# Display.net
KiCad netlist of a schematic drawn in Altium Designer
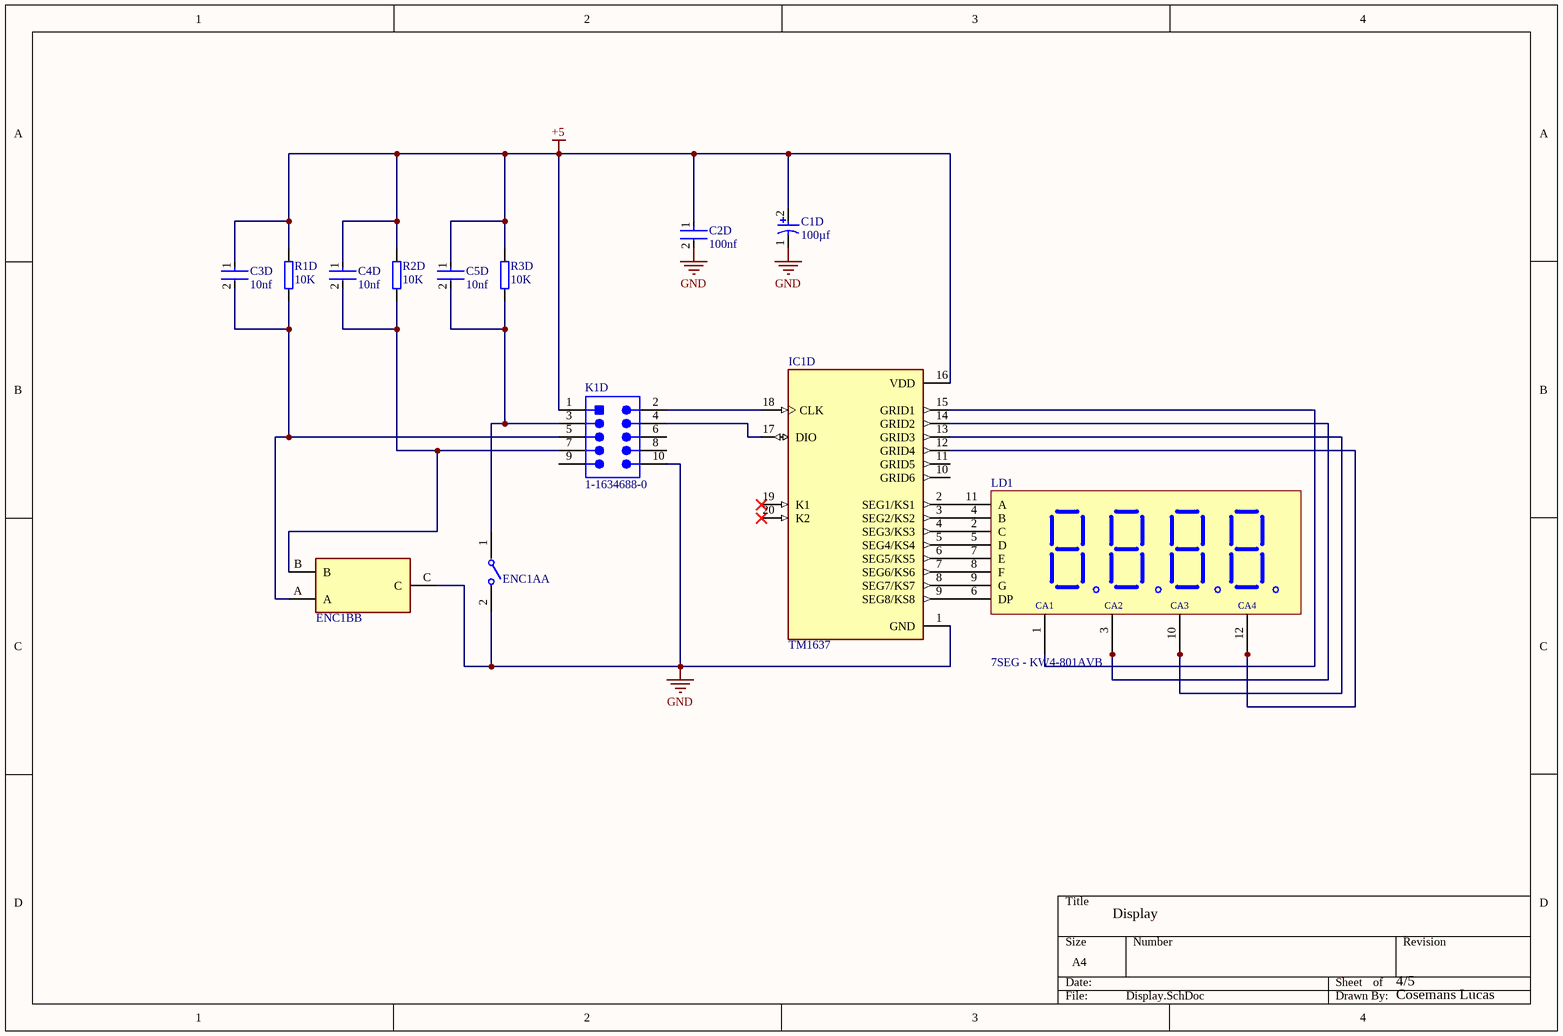
[diagram p0: Display.SchDoc]

(export (version "E")
  (design (tool "Eeschema 10.0.6"))
  (components
    (comp (ref "C1D")
      (value "100µf")
      (footprint "CE_D6,3_L4,5")
      (fields (field (name "MANUFACTURER") "Panasonic"))
      (libsource (lib "Schematic_soldeerstation") (part "Capacitor_Electrolytic"))
    )
    (comp (ref "C2D")
      (value "100nf")
      (footprint "CC_0805_L")
      (fields
        (field (name "MANUFACTURER") "KEMET")
        (field (name "OCTOPART") "https://octopart.com/c0805c224k5ractu-kemet-144670")
        (field (name "MANUFACTURER PART NUMBER") "C0805C224K5RACTU")
      )
      (libsource (lib "Schematic_soldeerstation") (part "Capacitor_Ceramic"))
    )
    (comp (ref "C3D")
      (value "10nf")
      (footprint "CC_0805_L")
      (fields
        (field (name "MANUFACTURER") "KEMET")
        (field (name "OCTOPART") "https://octopart.com/c0805c224k5ractu-kemet-144670")
        (field (name "MANUFACTURER PART NUMBER") "C0805C224K5RACTU")
      )
      (libsource (lib "Schematic_soldeerstation") (part "Capacitor_Ceramic"))
    )
    (comp (ref "C4D")
      (value "10nf")
      (footprint "CC_0805_L")
      (fields
        (field (name "MANUFACTURER") "KEMET")
        (field (name "OCTOPART") "https://octopart.com/c0805c224k5ractu-kemet-144670")
        (field (name "MANUFACTURER PART NUMBER") "C0805C224K5RACTU")
      )
      (libsource (lib "Schematic_soldeerstation") (part "Capacitor_Ceramic"))
    )
    (comp (ref "C5D")
      (value "10nf")
      (footprint "CC_0805_L")
      (fields
        (field (name "MANUFACTURER") "KEMET")
        (field (name "OCTOPART") "https://octopart.com/c0805c224k5ractu-kemet-144670")
        (field (name "MANUFACTURER PART NUMBER") "C0805C224K5RACTU")
      )
      (libsource (lib "Schematic_soldeerstation") (part "Capacitor_Ceramic"))
    )
    (comp (ref "ENC1A")
      (value "PEC11R-4220F-S0012")
      (footprint "PEC11R_4220F_S0012")
      (description "ROTARY ENCODER MECHANICAL 12PPR")
      (libsource (lib "Schematic_soldeerstation") (part "PEC11R-4220F-S0012"))
    )
    (comp (ref "ENC1B")
      (value "PEC11R-4220F-S0012")
      (footprint "PEC11R_4220F_S0012")
      (description "ROTARY ENCODER MECHANICAL 12PPR")
      (libsource (lib "") (part "PEC11R-4220F-S0012_1"))
    )
    (comp (ref "IC1D")
      (value "TM1637")
      (footprint "SOP_20_M")
      (description "LED Drive Control Special Circuit")
      (fields (field (name "MF") "Titan Micro Electronics"))
      (libsource (lib "Schematic_soldeerstation") (part "TM1637"))
    )
    (comp (ref "K1D")
      (value "1-1634688-0")
      (footprint "5x2 pin - TECO-1-1634688-0-10_V")
      (fields (field (name "MANUFACTURER") "TE Connectivity"))
      (libsource (lib "Schematic_soldeerstation") (part "5x2 Pin"))
    )
    (comp (ref "LD1")
      (value "7SEG - KW4-801AVB")
      (footprint "7SEG - ELF-5125")
      (description "4-Digit LED Display")
      (libsource (lib "Schematic_soldeerstation") (part "7SEG - KW4-801AVB"))
    )
    (comp (ref "R1D")
      (value "10K")
      (footprint "CC_0805_m")
      (fields (field (name "MANUFACTURER") "Vishay Dale") (field (name "PART NUMBER") "CRCW08050000Z0EA"))
      (libsource (lib "Schematic_soldeerstation") (part "Resistor"))
    )
    (comp (ref "R2D")
      (value "10K")
      (footprint "R_0805_M")
      (fields (field (name "MANUFACTURER") "Vishay Dale") (field (name "PART NUMBER") "CRCW08050000Z0EA"))
      (libsource (lib "Schematic_soldeerstation") (part "Resistor"))
    )
    (comp (ref "R3D")
      (value "10K")
      (footprint "R_0805_M")
      (fields (field (name "MANUFACTURER") "Vishay Dale") (field (name "PART NUMBER") "CRCW08050000Z0EA"))
      (libsource (lib "Schematic_soldeerstation") (part "Resistor"))
    )
  )
  (nets
    (net (code "1") (name "+5") (class "Default")
      (node (ref "C1D") (pin "2") (pinfunction "2_2") (pintype "passive"))
      (node (ref "C2D") (pin "1") (pinfunction "1_1") (pintype "passive"))
      (node (ref "C3D") (pin "1") (pinfunction "1_1") (pintype "passive"))
      (node (ref "C4D") (pin "1") (pinfunction "1_1") (pintype "passive"))
      (node (ref "C5D") (pin "1") (pinfunction "1_1") (pintype "passive"))
      (node (ref "IC1D") (pin "16") (pinfunction "VDD_16") (pintype "power_in"))
      (node (ref "K1D") (pin "1") (pinfunction "1_1") (pintype "passive"))
      (node (ref "R1D") (pin "2") (pinfunction "2_2") (pintype "passive"))
      (node (ref "R2D") (pin "2") (pinfunction "2_2") (pintype "passive"))
      (node (ref "R3D") (pin "2") (pinfunction "2_2") (pintype "passive"))
    )
    (net (code "2") (name "GND") (class "Default")
      (node (ref "C1D") (pin "1") (pinfunction "1_1") (pintype "passive"))
      (node (ref "C2D") (pin "2") (pinfunction "2_2") (pintype "passive"))
      (node (ref "ENC1A") (pin "2") (pinfunction "2_2") (pintype "passive"))
      (node (ref "ENC1B") (pin "C") (pinfunction "C_C") (pintype "passive"))
      (node (ref "IC1D") (pin "1") (pinfunction "GND_1") (pintype "power_in"))
      (node (ref "K1D") (pin "10") (pinfunction "10_10") (pintype "passive"))
    )
    (net (code "3") (name "Net-(C3D-Pad2)") (class "Default")
      (node (ref "C3D") (pin "2") (pinfunction "2_2") (pintype "passive"))
      (node (ref "ENC1B") (pin "A") (pinfunction "A_A") (pintype "passive"))
      (node (ref "K1D") (pin "5") (pinfunction "5_5") (pintype "passive"))
      (node (ref "R1D") (pin "1") (pinfunction "1_1") (pintype "passive"))
    )
    (net (code "4") (name "Net-(C4D-Pad2)") (class "Default")
      (node (ref "C4D") (pin "2") (pinfunction "2_2") (pintype "passive"))
      (node (ref "ENC1B") (pin "B") (pinfunction "B_B") (pintype "passive"))
      (node (ref "K1D") (pin "7") (pinfunction "7_7") (pintype "passive"))
      (node (ref "R2D") (pin "1") (pinfunction "1_1") (pintype "passive"))
    )
    (net (code "5") (name "Net-(C5D-Pad2)") (class "Default")
      (node (ref "C5D") (pin "2") (pinfunction "2_2") (pintype "passive"))
      (node (ref "ENC1A") (pin "1") (pinfunction "1_1") (pintype "passive"))
      (node (ref "K1D") (pin "3") (pinfunction "3_3") (pintype "passive"))
      (node (ref "R3D") (pin "1") (pinfunction "1_1") (pintype "passive"))
    )
    (net (code "6") (name "Net-(IC1D-CLK)") (class "Default")
      (node (ref "IC1D") (pin "18") (pinfunction "CLK_18") (pintype "input"))
      (node (ref "K1D") (pin "2") (pinfunction "2_2") (pintype "passive"))
    )
    (net (code "7") (name "Net-(IC1D-DIO)") (class "Default")
      (node (ref "IC1D") (pin "17") (pinfunction "DIO_17") (pintype "bidirectional"))
      (node (ref "K1D") (pin "4") (pinfunction "4_4") (pintype "passive"))
    )
    (net (code "8") (name "Net-(IC1D-GRID1)") (class "Default")
      (node (ref "IC1D") (pin "15") (pinfunction "GRID1_15") (pintype "output"))
      (node (ref "LD1") (pin "1") (pinfunction "CA1_1") (pintype "passive"))
    )
    (net (code "9") (name "Net-(IC1D-GRID2)") (class "Default")
      (node (ref "IC1D") (pin "14") (pinfunction "GRID2_14") (pintype "output"))
      (node (ref "LD1") (pin "3") (pinfunction "13_3") (pintype "passive"))
    )
    (net (code "10") (name "Net-(IC1D-GRID3)") (class "Default")
      (node (ref "IC1D") (pin "13") (pinfunction "GRID3_13") (pintype "output"))
      (node (ref "LD1") (pin "10") (pinfunction "14_10") (pintype "passive"))
    )
    (net (code "11") (name "Net-(IC1D-GRID4)") (class "Default")
      (node (ref "IC1D") (pin "12") (pinfunction "GRID4_12") (pintype "output"))
      (node (ref "LD1") (pin "12") (pinfunction "15_12") (pintype "passive"))
    )
    (net (code "12") (name "Net-(IC1D-SEG1{slash}KS1)") (class "Default")
      (node (ref "IC1D") (pin "2") (pinfunction "SEG1/KS1_2") (pintype "output"))
      (node (ref "LD1") (pin "11") (pinfunction "A_11") (pintype "passive"))
    )
    (net (code "13") (name "Net-(IC1D-SEG2{slash}KS2)") (class "Default")
      (node (ref "IC1D") (pin "3") (pinfunction "SEG2/KS2_3") (pintype "output"))
      (node (ref "LD1") (pin "4") (pinfunction "B_4") (pintype "passive"))
    )
    (net (code "14") (name "Net-(IC1D-SEG3{slash}KS3)") (class "Default")
      (node (ref "IC1D") (pin "4") (pinfunction "SEG3/KS3_4") (pintype "output"))
      (node (ref "LD1") (pin "2") (pinfunction "C_2") (pintype "passive"))
    )
    (net (code "15") (name "Net-(IC1D-SEG4{slash}KS4)") (class "Default")
      (node (ref "IC1D") (pin "5") (pinfunction "SEG4/KS4_5") (pintype "output"))
      (node (ref "LD1") (pin "5") (pinfunction "D_5") (pintype "passive"))
    )
    (net (code "16") (name "Net-(IC1D-SEG5{slash}KS5)") (class "Default")
      (node (ref "IC1D") (pin "6") (pinfunction "SEG5/KS5_6") (pintype "output"))
      (node (ref "LD1") (pin "7") (pinfunction "E_7") (pintype "passive"))
    )
    (net (code "17") (name "Net-(IC1D-SEG6{slash}KS6)") (class "Default")
      (node (ref "IC1D") (pin "7") (pinfunction "SEG6/KS6_7") (pintype "output"))
      (node (ref "LD1") (pin "8") (pinfunction "F_8") (pintype "passive"))
    )
    (net (code "18") (name "Net-(IC1D-SEG7{slash}KS7)") (class "Default")
      (node (ref "IC1D") (pin "8") (pinfunction "SEG7/KS7_8") (pintype "output"))
      (node (ref "LD1") (pin "9") (pinfunction "G_9") (pintype "passive"))
    )
    (net (code "19") (name "Net-(IC1D-SEG8{slash}KS8)") (class "Default")
      (node (ref "IC1D") (pin "9") (pinfunction "SEG8/KS8_9") (pintype "output"))
      (node (ref "LD1") (pin "6") (pinfunction "DP_6") (pintype "passive"))
    )
    (net (code "20") (name "unconnected-(IC1D-GRID5-Pad11)") (class "Default")
      (node (ref "IC1D") (pin "11") (pinfunction "GRID5_11") (pintype "output"))
    )
    (net (code "21") (name "unconnected-(IC1D-GRID6-Pad10)") (class "Default")
      (node (ref "IC1D") (pin "10") (pinfunction "GRID6_10") (pintype "output"))
    )
    (net (code "22") (name "unconnected-(IC1D-K1-Pad19)") (class "Default")
      (node (ref "IC1D") (pin "19") (pinfunction "K1_19") (pintype "input+no_connect"))
    )
    (net (code "23") (name "unconnected-(IC1D-K2-Pad20)") (class "Default")
      (node (ref "IC1D") (pin "20") (pinfunction "K2_20") (pintype "input+no_connect"))
    )
    (net (code "24") (name "unconnected-(K1D-Pad6)") (class "Default")
      (node (ref "K1D") (pin "6") (pinfunction "6_6") (pintype "passive"))
    )
    (net (code "25") (name "unconnected-(K1D-Pad8)") (class "Default")
      (node (ref "K1D") (pin "8") (pinfunction "8_8") (pintype "passive"))
    )
    (net (code "26") (name "unconnected-(K1D-Pad9)") (class "Default")
      (node (ref "K1D") (pin "9") (pinfunction "9_9") (pintype "passive"))
    )
  )
)
